# br17.net
KiCad netlist of a schematic drawn in Altium Designer
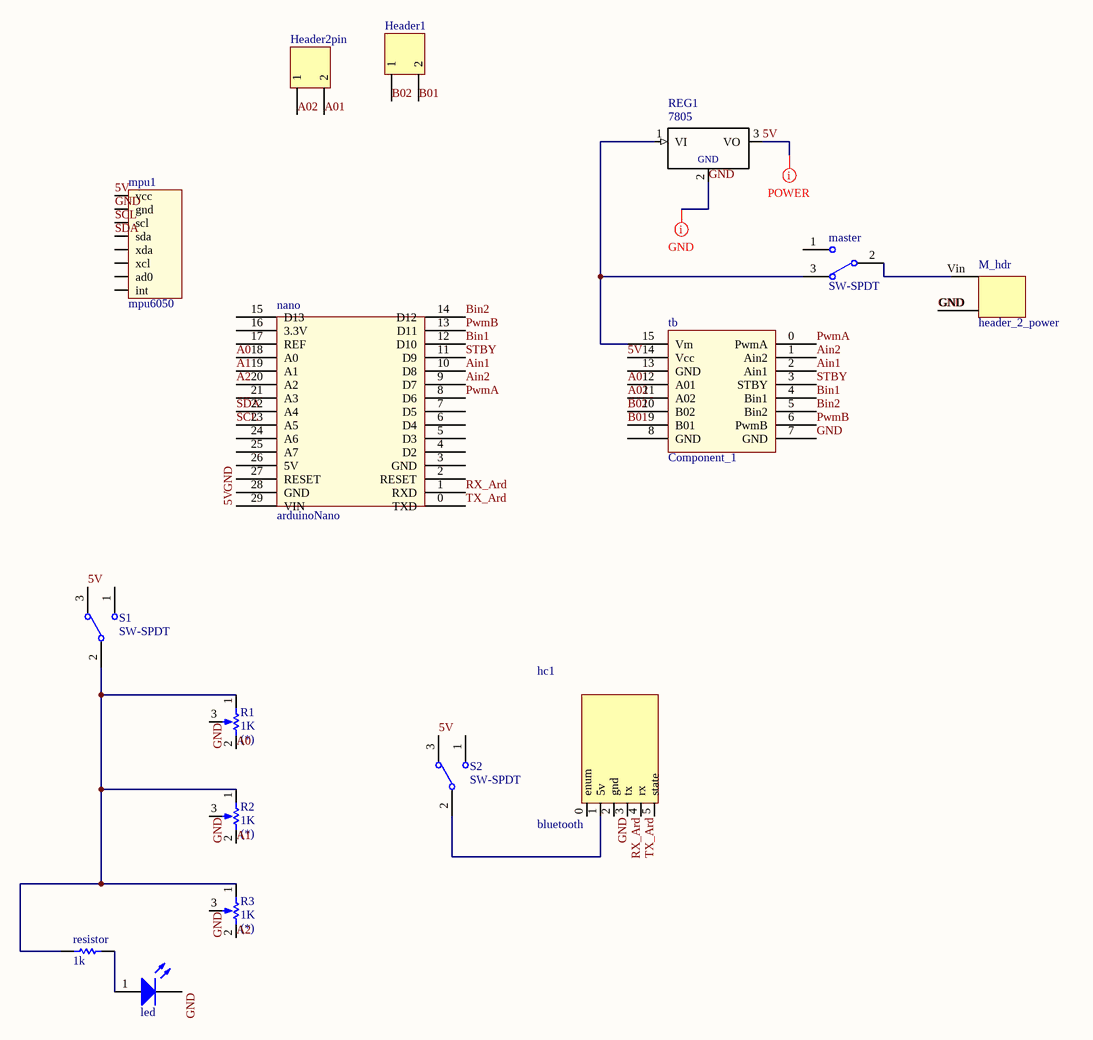
[diagram p0: br17.SchDoc]

(export (version "E")
  (design (tool "Eeschema 10.0.6"))
  (components
    (comp (ref "hc1")
      (value "bluetooth")
      (footprint "hc05")
      (description "bluetooth device hc 05")
      (libsource (lib "hc05") (part "hc05"))
    )
    (comp (ref "Header1")
      (value "Header 2")
      (footprint "HDR2_pin")
      (description "Header, 2-Pin")
      (fields (field (name "PUBLISHER") "Altium Limited"))
      (libsource (lib "headers") (part "Header 2"))
    )
    (comp (ref "Header2pin")
      (value "Header 2")
      (footprint "HDR2_pin")
      (description "Header, 2-Pin")
      (fields (field (name "PUBLISHER") "Altium Limited"))
      (libsource (lib "headers") (part "Header 2"))
    )
    (comp (ref "led")
      (value "L_green")
      (footprint "Led_green")
      (libsource (lib "Led_edited") (part "L_green"))
    )
    (comp (ref "master")
      (value "SW-SPDT")
      (footprint "SPDT")
      (description "SPDT Subminiature Toggle Switch, Right Angle Mounting, Vertical Actuation")
      (fields (field (name "PUBLISHER") "Altium Limited"))
      (libsource (lib "switches") (part "SW-SPDT"))
    )
    (comp (ref "mpu1")
      (value "mpu6050")
      (footprint "mpu6050")
      (description "this is mpu6050")
      (libsource (lib "mpu6050") (part "mpu6050"))
    )
    (comp (ref "M_hdr")
      (value "header_2_power")
      (footprint "HDR2_POWER")
      (libsource (lib "headers") (part "header_2_power"))
    )
    (comp (ref "nano")
      (value "arduinoNano")
      (footprint "Arduino nano")
      (libsource (lib "nanoArduino") (part "arduinoNano"))
    )
    (comp (ref "R1")
      (value "1K")
      (footprint "pot_alpha")
      (description "Potentiometer")
      (fields
        (field (name "TYPE") "(*)")
        (field (name "Comment") "ALPHA Potentiometer")
        (field (name "PUBLISHER") "Altium Limited")
      )
      (libsource (lib "potentiometers") (part "alpha-pot"))
    )
    (comp (ref "R2")
      (value "1K")
      (footprint "pot_alpha")
      (description "Potentiometer")
      (fields
        (field (name "TYPE") "(*)")
        (field (name "Comment") "ALPHA Potentiometer")
        (field (name "PUBLISHER") "Altium Limited")
      )
      (libsource (lib "potentiometers") (part "alpha-pot"))
    )
    (comp (ref "R3")
      (value "1K")
      (footprint "pot_alpha")
      (description "Potentiometer")
      (fields
        (field (name "TYPE") "(*)")
        (field (name "Comment") "ALPHA Potentiometer")
        (field (name "PUBLISHER") "Altium Limited")
      )
      (libsource (lib "potentiometers") (part "alpha-pot"))
    )
    (comp (ref "REG1")
      (value "7805")
      (footprint "TO92-")
      (description "Conn Quick Fit Header HDR 5 POS 5.1mm Solder RA Thru-Hole")
      (fields (field (name "MF") "Keystone"))
      (libsource (lib "7805") (part "7805"))
    )
    (comp (ref "resistor")
      (value "1k")
      (footprint "led")
      (fields (field (name "Comment") "resistance"))
      (libsource (lib "resistance") (part "resistance"))
    )
    (comp (ref "S1")
      (value "SW-SPDT")
      (footprint "SPDT")
      (description "SPDT Subminiature Toggle Switch, Right Angle Mounting, Vertical Actuation")
      (fields (field (name "PUBLISHER") "Altium Limited"))
      (libsource (lib "switches") (part "SW-SPDT"))
    )
    (comp (ref "S2")
      (value "SW-SPDT")
      (footprint "SPDT")
      (description "SPDT Subminiature Toggle Switch, Right Angle Mounting, Vertical Actuation")
      (fields (field (name "PUBLISHER") "Altium Limited"))
      (libsource (lib "switches") (part "SW-SPDT"))
    )
    (comp (ref "tb")
      (value "Component_1")
      (footprint "tb6612")
      (libsource (lib "tb6612_sparkfun") (part "Component_1"))
    )
  )
  (nets
    (net (code "1") (name "/5V") (class "Default")
      (node (ref "REG1") (pin "3") (pinfunction "VO_3") (pintype "passive"))
      (node (ref "S1") (pin "3") (pinfunction "3_3") (pintype "passive"))
      (node (ref "S2") (pin "3") (pinfunction "3_3") (pintype "passive"))
      (node (ref "mpu1") (pin "0") (pinfunction "vcc_0") (pintype "passive"))
      (node (ref "nano") (pin "29") (pinfunction "VIN_29") (pintype "passive"))
      (node (ref "tb") (pin "14") (pinfunction "Vcc_14") (pintype "passive"))
    )
    (net (code "2") (name "/A0") (class "Default")
      (node (ref "R1") (pin "2") (pinfunction "BOT_2") (pintype "passive"))
      (node (ref "nano") (pin "18") (pinfunction "A0_18") (pintype "passive"))
    )
    (net (code "3") (name "/A01") (class "Default")
      (node (ref "Header2pin") (pin "2") (pinfunction "2_2") (pintype "passive"))
      (node (ref "tb") (pin "12") (pinfunction "A01_12") (pintype "passive"))
    )
    (net (code "4") (name "/A1") (class "Default")
      (node (ref "R2") (pin "2") (pinfunction "BOT_2") (pintype "passive"))
      (node (ref "nano") (pin "19") (pinfunction "A1_19") (pintype "passive"))
    )
    (net (code "5") (name "/A02") (class "Default")
      (node (ref "Header2pin") (pin "1") (pinfunction "1_1") (pintype "passive"))
      (node (ref "tb") (pin "11") (pinfunction "A02_11") (pintype "passive"))
    )
    (net (code "6") (name "/A2") (class "Default")
      (node (ref "R3") (pin "2") (pinfunction "BOT_2") (pintype "passive"))
      (node (ref "nano") (pin "20") (pinfunction "A2_20") (pintype "passive"))
    )
    (net (code "7") (name "/Ain1") (class "Default")
      (node (ref "nano") (pin "10") (pinfunction "D8_10") (pintype "passive"))
      (node (ref "tb") (pin "2") (pinfunction "Ain1_2") (pintype "passive"))
    )
    (net (code "8") (name "/Ain2") (class "Default")
      (node (ref "nano") (pin "9") (pinfunction "D7_9") (pintype "passive"))
      (node (ref "tb") (pin "1") (pinfunction "Ain2_1") (pintype "passive"))
    )
    (net (code "9") (name "/B01") (class "Default")
      (node (ref "Header1") (pin "2") (pinfunction "2_2") (pintype "passive"))
      (node (ref "tb") (pin "9") (pinfunction "B01_9") (pintype "passive"))
    )
    (net (code "10") (name "/B02") (class "Default")
      (node (ref "Header1") (pin "1") (pinfunction "1_1") (pintype "passive"))
      (node (ref "tb") (pin "10") (pinfunction "B02_10") (pintype "passive"))
    )
    (net (code "11") (name "/Bin1") (class "Default")
      (node (ref "nano") (pin "12") (pinfunction "D10_12") (pintype "passive"))
      (node (ref "tb") (pin "4") (pinfunction "Bin1_4") (pintype "passive"))
    )
    (net (code "12") (name "/Bin2") (class "Default")
      (node (ref "nano") (pin "14") (pinfunction "D12_14") (pintype "passive"))
      (node (ref "tb") (pin "5") (pinfunction "Bin2_5") (pintype "passive"))
    )
    (net (code "13") (name "/GND") (class "Default")
      (node (ref "M_hdr") (pin "GND") (pinfunction "2_GND") (pintype "passive"))
      (node (ref "R1") (pin "3") (pinfunction "TAP_3") (pintype "passive"))
      (node (ref "R2") (pin "3") (pinfunction "TAP_3") (pintype "passive"))
      (node (ref "R3") (pin "3") (pinfunction "TAP_3") (pintype "passive"))
      (node (ref "REG1") (pin "2") (pinfunction "GND_2") (pintype "passive"))
      (node (ref "hc1") (pin "2") (pinfunction "gnd_2") (pintype "passive"))
      (node (ref "led") (pin "2") (pinfunction "K_2") (pintype "passive"))
      (node (ref "mpu1") (pin "1") (pinfunction "gnd_1") (pintype "passive"))
      (node (ref "nano") (pin "28") (pinfunction "GND_28") (pintype "passive"))
      (node (ref "tb") (pin "7") (pinfunction "GND_7") (pintype "passive"))
    )
    (net (code "14") (name "/PwmA") (class "Default")
      (node (ref "nano") (pin "8") (pinfunction "D6_8") (pintype "passive"))
      (node (ref "tb") (pin "0") (pinfunction "PwmA_0") (pintype "passive"))
    )
    (net (code "15") (name "/PwmB") (class "Default")
      (node (ref "nano") (pin "13") (pinfunction "D11_13") (pintype "passive"))
      (node (ref "tb") (pin "6") (pinfunction "PwmB_6") (pintype "passive"))
    )
    (net (code "16") (name "/RX_Ard") (class "Default")
      (node (ref "hc1") (pin "3") (pinfunction "tx_3") (pintype "passive"))
      (node (ref "nano") (pin "1") (pinfunction "RXD_1") (pintype "passive"))
    )
    (net (code "17") (name "/SCL") (class "Default")
      (node (ref "mpu1") (pin "2") (pinfunction "scl_2") (pintype "passive"))
      (node (ref "nano") (pin "23") (pinfunction "A5_23") (pintype "passive"))
    )
    (net (code "18") (name "/SDA") (class "Default")
      (node (ref "mpu1") (pin "3") (pinfunction "sda_3") (pintype "passive"))
      (node (ref "nano") (pin "22") (pinfunction "A4_22") (pintype "passive"))
    )
    (net (code "19") (name "/STBY") (class "Default")
      (node (ref "nano") (pin "11") (pinfunction "D9_11") (pintype "passive"))
      (node (ref "tb") (pin "3") (pinfunction "STBY_3") (pintype "passive"))
    )
    (net (code "20") (name "/TX_Ard") (class "Default")
      (node (ref "hc1") (pin "4") (pinfunction "rx_4") (pintype "passive"))
      (node (ref "nano") (pin "0") (pinfunction "TXD_0") (pintype "passive"))
    )
    (net (code "21") (name "Net-(M_hdr-1)") (class "Default")
      (node (ref "M_hdr") (pin "Vin") (pinfunction "1_Vin") (pintype "passive"))
      (node (ref "master") (pin "2") (pinfunction "2_2") (pintype "passive"))
    )
    (net (code "22") (name "Net-(R1-TOP)") (class "Default")
      (node (ref "R1") (pin "1") (pinfunction "TOP_1") (pintype "passive"))
      (node (ref "R2") (pin "1") (pinfunction "TOP_1") (pintype "passive"))
      (node (ref "R3") (pin "1") (pinfunction "TOP_1") (pintype "passive"))
      (node (ref "S1") (pin "2") (pinfunction "2_2") (pintype "passive"))
      (node (ref "resistor") (pin "1") (pinfunction "1_1") (pintype "passive"))
    )
    (net (code "23") (name "Net-(REG1-VI)") (class "Default")
      (node (ref "REG1") (pin "1") (pinfunction "VI_1") (pintype "input"))
      (node (ref "master") (pin "3") (pinfunction "3_3") (pintype "passive"))
      (node (ref "tb") (pin "15") (pinfunction "Vm_15") (pintype "passive"))
    )
    (net (code "24") (name "Net-(hc1-5v)") (class "Default")
      (node (ref "S2") (pin "2") (pinfunction "2_2") (pintype "passive"))
      (node (ref "hc1") (pin "1") (pinfunction "5v_1") (pintype "passive"))
    )
    (net (code "25") (name "Net-(led-V)") (class "Default")
      (node (ref "led") (pin "1") (pinfunction "V_1") (pintype "passive"))
      (node (ref "resistor") (pin "2") (pinfunction "2_2") (pintype "passive"))
    )
    (net (code "26") (name "unconnected-(S1-Pad1)") (class "Default")
      (node (ref "S1") (pin "1") (pinfunction "1_1") (pintype "passive"))
    )
    (net (code "27") (name "unconnected-(S2-Pad1)") (class "Default")
      (node (ref "S2") (pin "1") (pinfunction "1_1") (pintype "passive"))
    )
    (net (code "28") (name "unconnected-(hc1-enum-Pad0)") (class "Default")
      (node (ref "hc1") (pin "0") (pinfunction "enum_0") (pintype "passive"))
    )
    (net (code "29") (name "unconnected-(hc1-state-Pad5)") (class "Default")
      (node (ref "hc1") (pin "5") (pinfunction "state_5") (pintype "passive"))
    )
    (net (code "30") (name "unconnected-(master-Pad1)") (class "Default")
      (node (ref "master") (pin "1") (pinfunction "1_1") (pintype "passive"))
    )
    (net (code "31") (name "unconnected-(mpu1-ad0-Pad6)") (class "Default")
      (node (ref "mpu1") (pin "6") (pinfunction "ad0_6") (pintype "passive"))
    )
    (net (code "32") (name "unconnected-(mpu1-int-Pad7)") (class "Default")
      (node (ref "mpu1") (pin "7") (pinfunction "int_7") (pintype "passive"))
    )
    (net (code "33") (name "unconnected-(mpu1-xcl-Pad5)") (class "Default")
      (node (ref "mpu1") (pin "5") (pinfunction "xcl_5") (pintype "passive"))
    )
    (net (code "34") (name "unconnected-(mpu1-xda-Pad4)") (class "Default")
      (node (ref "mpu1") (pin "4") (pinfunction "xda_4") (pintype "passive"))
    )
    (net (code "35") (name "unconnected-(nano-3.3V-Pad16)") (class "Default")
      (node (ref "nano") (pin "16") (pinfunction "3.3V_16") (pintype "passive"))
    )
    (net (code "36") (name "unconnected-(nano-5V-Pad26)") (class "Default")
      (node (ref "nano") (pin "26") (pinfunction "5V_26") (pintype "passive"))
    )
    (net (code "37") (name "unconnected-(nano-A3-Pad21)") (class "Default")
      (node (ref "nano") (pin "21") (pinfunction "A3_21") (pintype "passive"))
    )
    (net (code "38") (name "unconnected-(nano-A6-Pad24)") (class "Default")
      (node (ref "nano") (pin "24") (pinfunction "A6_24") (pintype "passive"))
    )
    (net (code "39") (name "unconnected-(nano-A7-Pad25)") (class "Default")
      (node (ref "nano") (pin "25") (pinfunction "A7_25") (pintype "passive"))
    )
    (net (code "40") (name "unconnected-(nano-D2-Pad4)") (class "Default")
      (node (ref "nano") (pin "4") (pinfunction "D2_4") (pintype "passive"))
    )
    (net (code "41") (name "unconnected-(nano-D3-Pad5)") (class "Default")
      (node (ref "nano") (pin "5") (pinfunction "D3_5") (pintype "passive"))
    )
    (net (code "42") (name "unconnected-(nano-D4-Pad6)") (class "Default")
      (node (ref "nano") (pin "6") (pinfunction "D4_6") (pintype "passive"))
    )
    (net (code "43") (name "unconnected-(nano-D5-Pad7)") (class "Default")
      (node (ref "nano") (pin "7") (pinfunction "D5_7") (pintype "passive"))
    )
    (net (code "44") (name "unconnected-(nano-D13-Pad15)") (class "Default")
      (node (ref "nano") (pin "15") (pinfunction "D13_15") (pintype "passive"))
    )
    (net (code "45") (name "unconnected-(nano-GND-Pad3)") (class "Default")
      (node (ref "nano") (pin "3") (pinfunction "GND_3") (pintype "passive"))
    )
    (net (code "46") (name "unconnected-(nano-REF-Pad17)") (class "Default")
      (node (ref "nano") (pin "17") (pinfunction "REF_17") (pintype "passive"))
    )
    (net (code "47") (name "unconnected-(nano-RESET-Pad2)") (class "Default")
      (node (ref "nano") (pin "2") (pinfunction "RESET_2") (pintype "passive"))
    )
    (net (code "48") (name "unconnected-(nano-RESET-Pad27)") (class "Default")
      (node (ref "nano") (pin "27") (pinfunction "RESET_27") (pintype "passive"))
    )
    (net (code "49") (name "unconnected-(tb-GND-Pad8)") (class "Default")
      (node (ref "tb") (pin "8") (pinfunction "GND_8") (pintype "passive"))
    )
    (net (code "50") (name "unconnected-(tb-GND-Pad13)") (class "Default")
      (node (ref "tb") (pin "13") (pinfunction "GND_13") (pintype "passive"))
    )
  )
)
